# receiver.net
KiCad netlist of a schematic drawn in EAGLE
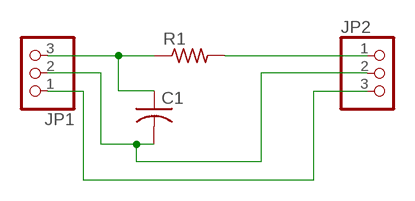
[diagram p0: schematic, sheet 1]

(export (version "E")
  (design (tool "Eeschema 10.0.6"))
  (components
    (comp (ref "C1")
      (value "C-US025-030X050")
      (footprint "eagle-import:C025-030X050")
      (libsource (lib "eagle-import") (part "C-US025-030X050"))
    )
    (comp (ref "JP1")
      (value "PINHD-1X3")
      (footprint "eagle-import:1X03")
      (libsource (lib "eagle-import") (part "PINHD-1X3"))
    )
    (comp (ref "JP2")
      (value "PINHD-1X3")
      (footprint "eagle-import:1X03")
      (libsource (lib "eagle-import") (part "PINHD-1X3"))
    )
    (comp (ref "R1")
      (value "R-US_0207/12")
      (footprint "eagle-import:0207_12")
      (libsource (lib "eagle-import") (part "R-US_0207/12"))
    )
  )
  (nets
    (net (code "1") (name "Net-(C1-Pad1)") (class "Default")
      (node (ref "C1") (pin "1") (pinfunction "1_1") (pintype "passive"))
      (node (ref "JP1") (pin "3") (pinfunction "3_3") (pintype "passive"))
      (node (ref "R1") (pin "1") (pinfunction "1_1") (pintype "passive"))
    )
    (net (code "2") (name "Net-(C1-Pad2)") (class "Default")
      (node (ref "C1") (pin "2") (pinfunction "2_2") (pintype "passive"))
      (node (ref "JP1") (pin "2") (pinfunction "2_2") (pintype "passive"))
      (node (ref "JP2") (pin "2") (pinfunction "2_2") (pintype "passive"))
    )
    (net (code "3") (name "Net-(JP1-Pad1)") (class "Default")
      (node (ref "JP1") (pin "1") (pinfunction "1_1") (pintype "passive"))
      (node (ref "JP2") (pin "3") (pinfunction "3_3") (pintype "passive"))
    )
    (net (code "4") (name "Net-(JP2-Pad1)") (class "Default")
      (node (ref "JP2") (pin "1") (pinfunction "1_1") (pintype "passive"))
      (node (ref "R1") (pin "2") (pinfunction "2_2") (pintype "passive"))
    )
  )
)
